# MCU.net
KiCad netlist of a schematic drawn in Altium Designer
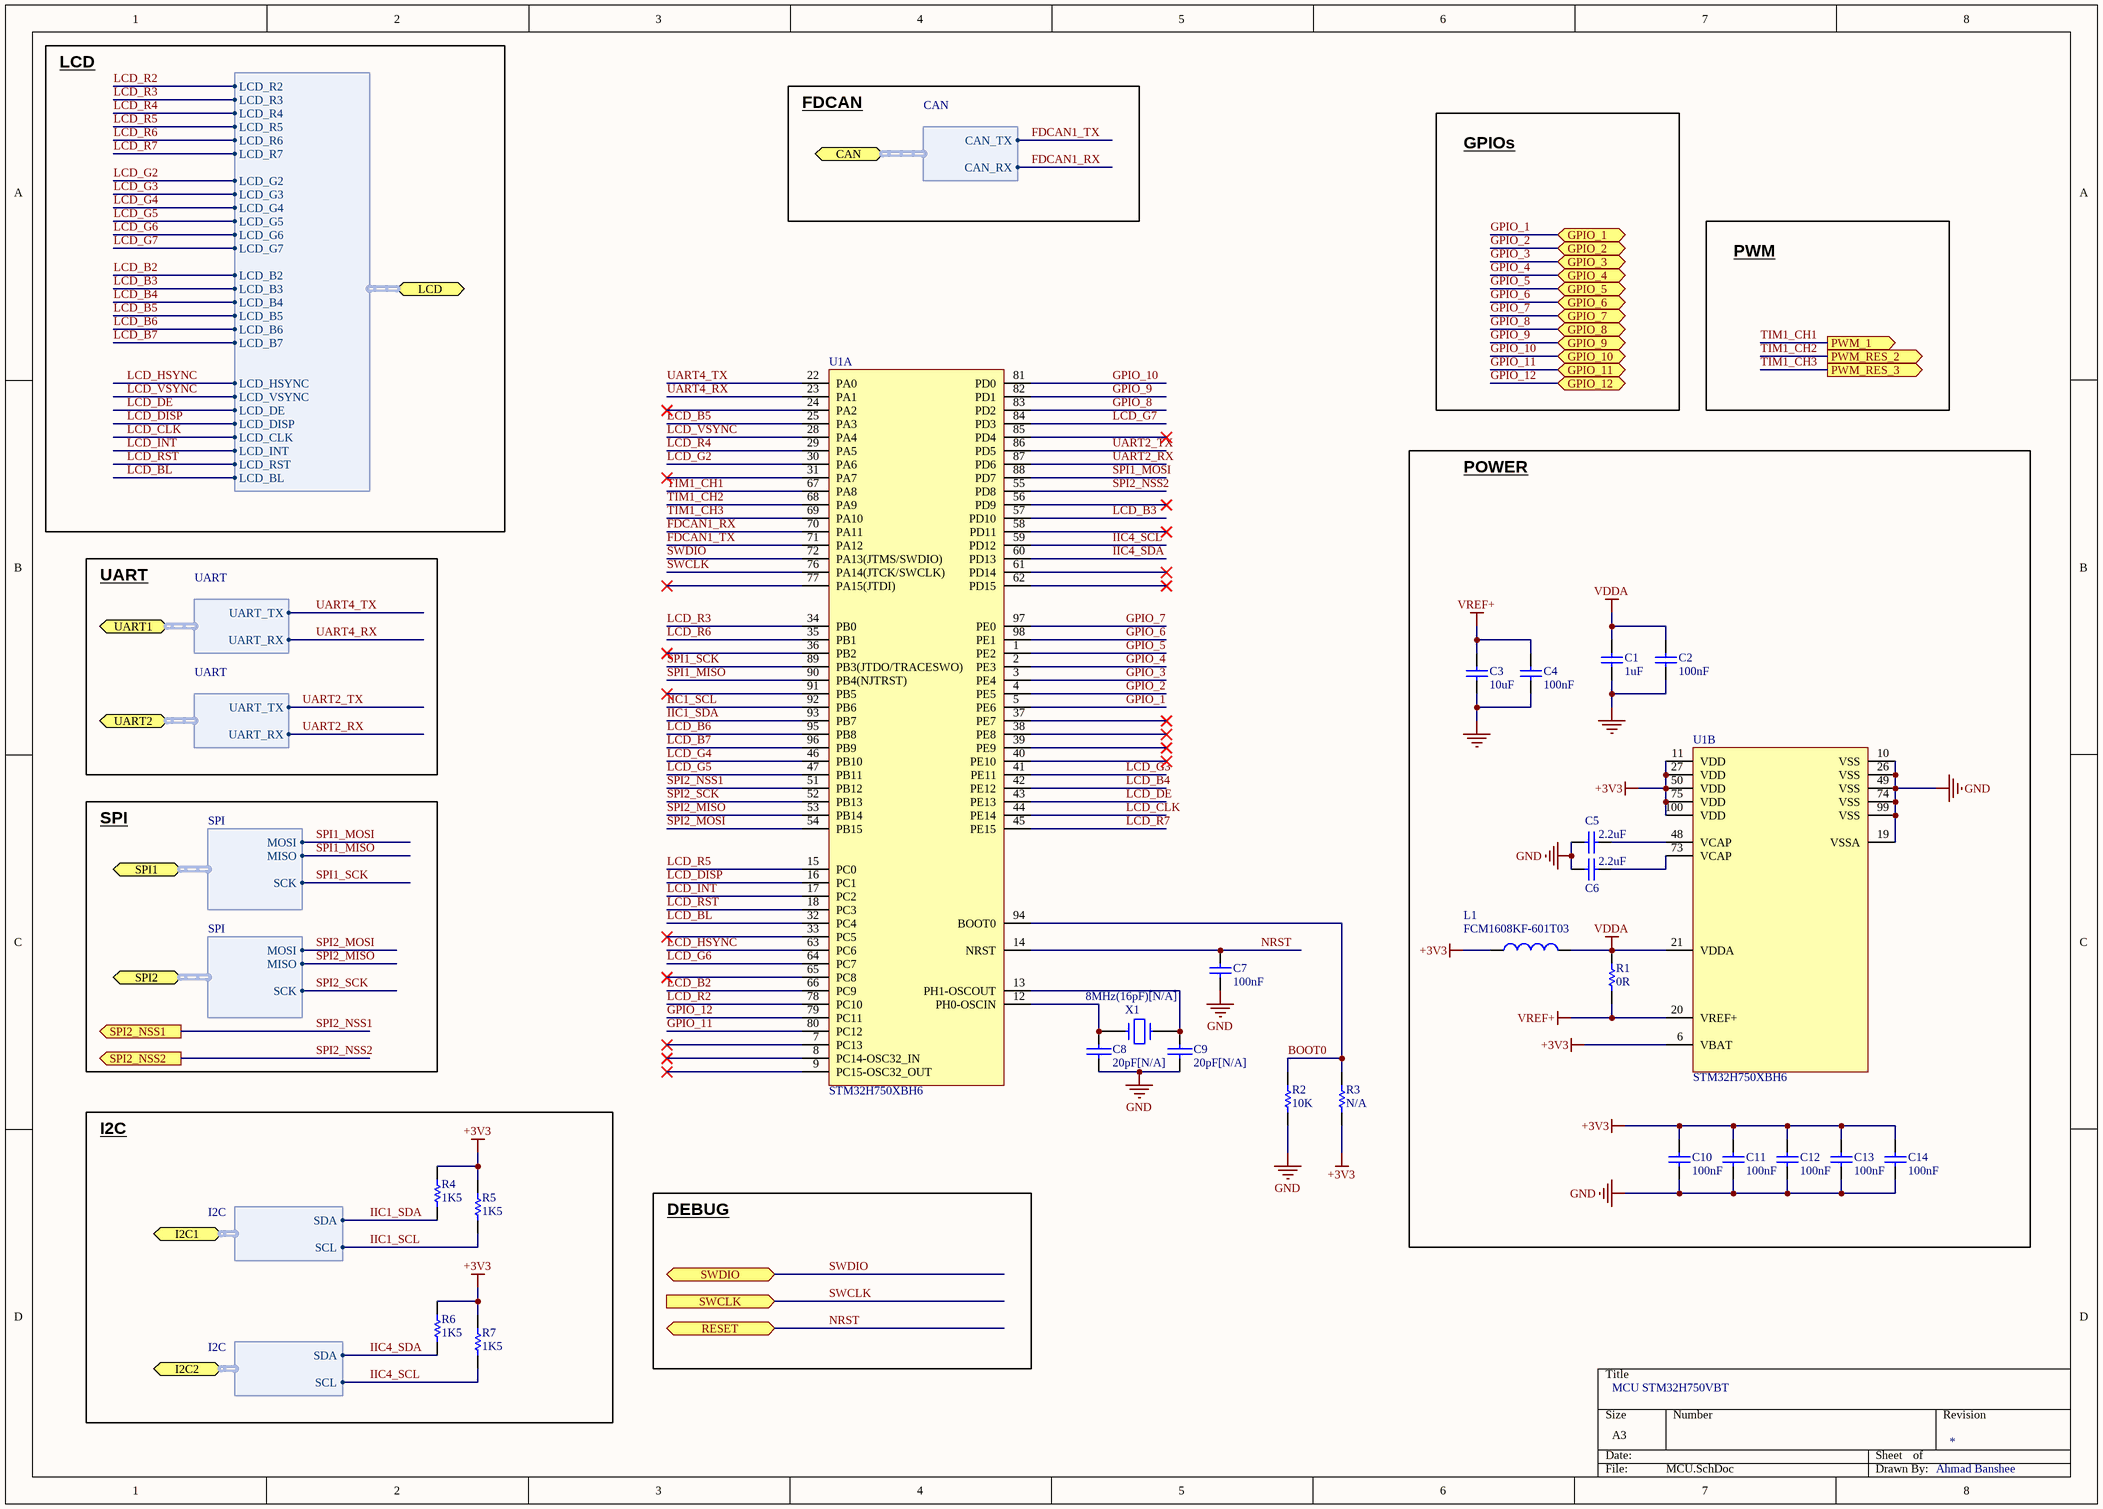
[diagram p0: MCU.SchDoc]

(export (version "E")
  (design (tool "Eeschema 10.0.6"))
  (components
    (comp (ref "C1")
      (value "1uF")
      (footprint "0805C-ST")
      (description "Capacitor, MLCC, 10uF, 25V, X5R, 10%, 0805, T=0,85mm")
      (fields
        (field (name "INTERNAL_PART_NUMBER") "MCD-00014")
        (field (name "MANUFACTURER_PART_NUMBER") "CC0805KRX5R8BB106")
        (field (name "PROVIDED_BY") "Subcon")
      )
      (libsource (lib "MCD_PARTS_database") (part "Capacitor"))
    )
    (comp (ref "C2")
      (value "100nF")
      (footprint "0603C ST")
      (description "Capacitor, MLCC, 100nF, 16V, X7R, 10%, 0402, T=0,5mm")
      (fields
        (field (name "INTERNAL_PART_NUMBER") "MCD-00102")
        (field (name "MANUFACTURER_PART_NUMBER") "CC0402KRX7R7BB104")
        (field (name "PROVIDED_BY") "Subcon")
      )
      (libsource (lib "MCD_PARTS_database") (part "Capacitor"))
    )
    (comp (ref "C3")
      (value "10uF")
      (footprint "0805C-ST")
      (description "Capacitor, MLCC, 10uF, 25V, X5R, 10%, 0805, T=0,85mm")
      (fields
        (field (name "INTERNAL_PART_NUMBER") "MCD-00014")
        (field (name "MANUFACTURER_PART_NUMBER") "CC0805KRX5R8BB106")
        (field (name "PROVIDED_BY") "Subcon")
      )
      (libsource (lib "MCD_PARTS_database") (part "Capacitor"))
    )
    (comp (ref "C4")
      (value "100nF")
      (footprint "0603C ST")
      (description "Capacitor, MLCC, 100nF, 16V, X7R, 10%, 0402, T=0,5mm")
      (fields
        (field (name "INTERNAL_PART_NUMBER") "MCD-00102")
        (field (name "MANUFACTURER_PART_NUMBER") "CC0402KRX7R7BB104")
        (field (name "PROVIDED_BY") "Subcon")
      )
      (libsource (lib "MCD_PARTS_database") (part "Capacitor"))
    )
    (comp (ref "C5")
      (value "2.2uF")
      (footprint "0603C-ST")
      (description "Capacitor, MLCC, 2.2uF, 10V, X5R, 10%, 0603, T=0,8mm")
      (fields
        (field (name "INTERNAL_PART_NUMBER") "MCD-00012")
        (field (name "MANUFACTURER_PART_NUMBER") "CC0603KRX5R6BB225")
        (field (name "PROVIDED_BY") "Subcon")
      )
      (libsource (lib "MCD_PARTS_database") (part "Capacitor"))
    )
    (comp (ref "C6")
      (value "2.2uF")
      (footprint "0603C-ST")
      (description "Capacitor, MLCC, 2.2uF, 10V, X5R, 10%, 0603, T=0,8mm")
      (fields
        (field (name "INTERNAL_PART_NUMBER") "MCD-00012")
        (field (name "MANUFACTURER_PART_NUMBER") "CC0603KRX5R6BB225")
        (field (name "PROVIDED_BY") "Subcon")
      )
      (libsource (lib "MCD_PARTS_database") (part "Capacitor"))
    )
    (comp (ref "C7")
      (value "100nF")
      (footprint "0603C ST")
      (description "Capacitor")
      (fields (field (name "PUBLISHER") "Altium Limited"))
      (libsource (lib "Miscellaneous Devices") (part "Cap"))
    )
    (comp (ref "C8")
      (value "20pF[N/A]")
      (footprint "0603C ST")
      (description "Capacitor")
      (libsource (lib "*") (part "CAP"))
    )
    (comp (ref "C9")
      (value "20pF[N/A]")
      (footprint "0603C ST")
      (description "Capacitor")
      (libsource (lib "*") (part "CAP"))
    )
    (comp (ref "C10")
      (value "100nF")
      (footprint "0603C ST")
      (description "Capacitor, MLCC, 100nF, 16V, X7R, 10%, 0402, T=0,5mm")
      (fields
        (field (name "INTERNAL_PART_NUMBER") "MCD-00102")
        (field (name "MANUFACTURER_PART_NUMBER") "CC0402KRX7R7BB104")
        (field (name "PROVIDED_BY") "Subcon")
      )
      (libsource (lib "MCD_PARTS_database") (part "Capacitor"))
    )
    (comp (ref "C11")
      (value "100nF")
      (footprint "0603C ST")
      (description "Capacitor, MLCC, 100nF, 16V, X7R, 10%, 0402, T=0,5mm")
      (fields
        (field (name "INTERNAL_PART_NUMBER") "MCD-00102")
        (field (name "MANUFACTURER_PART_NUMBER") "CC0402KRX7R7BB104")
        (field (name "PROVIDED_BY") "Subcon")
      )
      (libsource (lib "MCD_PARTS_database") (part "Capacitor"))
    )
    (comp (ref "C12")
      (value "100nF")
      (footprint "0603C ST")
      (description "Capacitor, MLCC, 100nF, 16V, X7R, 10%, 0402, T=0,5mm")
      (fields
        (field (name "INTERNAL_PART_NUMBER") "MCD-00102")
        (field (name "MANUFACTURER_PART_NUMBER") "CC0402KRX7R7BB104")
        (field (name "PROVIDED_BY") "Subcon")
      )
      (libsource (lib "MCD_PARTS_database") (part "Capacitor"))
    )
    (comp (ref "C13")
      (value "100nF")
      (footprint "0603C ST")
      (description "Capacitor, MLCC, 100nF, 16V, X7R, 10%, 0402, T=0,5mm")
      (fields
        (field (name "INTERNAL_PART_NUMBER") "MCD-00102")
        (field (name "MANUFACTURER_PART_NUMBER") "CC0402KRX7R7BB104")
        (field (name "PROVIDED_BY") "Subcon")
      )
      (libsource (lib "MCD_PARTS_database") (part "Capacitor"))
    )
    (comp (ref "C14")
      (value "100nF")
      (footprint "0603C ST")
      (description "Capacitor, MLCC, 100nF, 16V, X7R, 10%, 0402, T=0,5mm")
      (fields
        (field (name "INTERNAL_PART_NUMBER") "MCD-00102")
        (field (name "MANUFACTURER_PART_NUMBER") "CC0402KRX7R7BB104")
        (field (name "PROVIDED_BY") "Subcon")
      )
      (libsource (lib "MCD_PARTS_database") (part "Capacitor"))
    )
    (comp (ref "L1")
      (value "BEAD")
      (footprint "0603L-ST")
      (description "SMD Chip ferrite bead, 600R@100MHz +/-25%, 350mA, 500mohm DC, 0603, T=0.8mm")
      (fields
        (field (name "INTERNAL_PART_NUMBER") "MCD-00047")
        (field (name "MANUFACTURER_PART_NUMBER") "FCM1608KF-601T03")
        (field (name "MANUFACTURER") "TAI-TECH")
        (field (name "PROVIDED_BY") "Subcon")
      )
      (libsource (lib "MCD_PARTS_database") (part "BEAD"))
    )
    (comp (ref "R1")
      (value "0R")
      (footprint "0603R")
      (description "Resistor,0R,0603,ULO")
      (fields
        (field (name "INTERNAL_PART_NUMBER") "MCD-00181")
        (field (name "MANUFACTURER_PART_NUMBER") "PMR03EZPJ000")
        (field (name "PROVIDED_BY") "Subcon")
      )
      (libsource (lib "MCD_PARTS_database") (part "Resistor"))
    )
    (comp (ref "R2")
      (value "10K")
      (footprint "0603R")
      (description "Resistor,10K,0402,1%,1/16W")
      (fields
        (field (name "INTERNAL_PART_NUMBER") "MCD-00053")
        (field (name "MANUFACTURER_PART_NUMBER") "RC0402FR-0710KL")
        (field (name "PROVIDED_BY") "subcon")
      )
      (libsource (lib "MCD_PARTS_database") (part "Resistor"))
    )
    (comp (ref "R3")
      (value "N/A")
      (footprint "0603R")
      (description "Resistor,10K,0402,1%,1/16W")
      (fields
        (field (name "INTERNAL_PART_NUMBER") "MCD-00053")
        (field (name "MANUFACTURER_PART_NUMBER") "RC0402FR-0710KL")
        (field (name "PROVIDED_BY") "subcon")
      )
      (libsource (lib "MCD_PARTS_database") (part "Resistor"))
    )
    (comp (ref "R4")
      (value "1K5")
      (footprint "0603R")
      (description "Resistor,1K5,0402,1%,1/16W")
      (fields
        (field (name "INTERNAL_PART_NUMBER") "MCD-00068")
        (field (name "MANUFACTURER_PART_NUMBER") "RC0402FR-071K5L")
        (field (name "PROVIDED_BY") "Subcon")
      )
      (libsource (lib "MCD_PARTS_database") (part "Resistor"))
    )
    (comp (ref "R5")
      (value "1K5")
      (footprint "0603R")
      (description "Resistor,1K5,0402,1%,1/16W")
      (fields
        (field (name "INTERNAL_PART_NUMBER") "MCD-00068")
        (field (name "MANUFACTURER_PART_NUMBER") "RC0402FR-071K5L")
        (field (name "PROVIDED_BY") "Subcon")
      )
      (libsource (lib "MCD_PARTS_database") (part "Resistor"))
    )
    (comp (ref "R6")
      (value "1K5")
      (footprint "0603R")
      (description "Resistor,1K5,0402,1%,1/16W")
      (fields
        (field (name "INTERNAL_PART_NUMBER") "MCD-00068")
        (field (name "MANUFACTURER_PART_NUMBER") "RC0402FR-071K5L")
        (field (name "PROVIDED_BY") "Subcon")
      )
      (libsource (lib "MCD_PARTS_database") (part "Resistor"))
    )
    (comp (ref "R7")
      (value "1K5")
      (footprint "0603R")
      (description "Resistor,1K5,0402,1%,1/16W")
      (fields
        (field (name "INTERNAL_PART_NUMBER") "MCD-00068")
        (field (name "MANUFACTURER_PART_NUMBER") "RC0402FR-071K5L")
        (field (name "PROVIDED_BY") "Subcon")
      )
      (libsource (lib "MCD_PARTS_database") (part "Resistor"))
    )
    (comp (ref "U1")
      (value "STM32H750XBH6")
      (footprint "LQFP100_M")
      (description "32bit MCU TFBGA240+25")
      (fields
        (field (name "INTERNAL_PART_NUMBER") "MCD-01085")
        (field (name "MANUFACTURER_PART_NUMBER") "STM32H745XIH6")
        (field (name "PROVIDED_BY") "STM")
      )
      (libsource (lib "MB1381") (part "STM32H750VBT"))
    )
    (comp (ref "X1")
      (value "8MHz(16pF)[N/A]")
      (footprint "XTAL1")
      (description "Crystal")
      (libsource (lib "*") (part "CRYSTAL"))
    )
  )
  (nets
    (net (code "6") (name "+3V3") (class "Default")
      (node (ref "C10") (pin "2") (pinfunction "2_2") (pintype "passive"))
      (node (ref "C11") (pin "2") (pinfunction "2_2") (pintype "passive"))
      (node (ref "C12") (pin "2") (pinfunction "2_2") (pintype "passive"))
      (node (ref "C13") (pin "2") (pinfunction "2_2") (pintype "passive"))
      (node (ref "C14") (pin "2") (pinfunction "2_2") (pintype "passive"))
      (node (ref "L1") (pin "1") (pinfunction "1_1") (pintype "passive"))
      (node (ref "R3") (pin "1") (pinfunction "1_1") (pintype "passive"))
      (node (ref "R4") (pin "2") (pinfunction "2_2") (pintype "passive"))
      (node (ref "R5") (pin "2") (pinfunction "2_2") (pintype "passive"))
      (node (ref "R6") (pin "2") (pinfunction "2_2") (pintype "passive"))
      (node (ref "R7") (pin "2") (pinfunction "2_2") (pintype "passive"))
      (node (ref "U1") (pin "100") (pinfunction "VDD_100") (pintype "passive"))
      (node (ref "U1") (pin "11") (pinfunction "VDD_11") (pintype "passive"))
      (node (ref "U1") (pin "27") (pinfunction "VDD_27") (pintype "passive"))
      (node (ref "U1") (pin "50") (pinfunction "VDD_50") (pintype "passive"))
      (node (ref "U1") (pin "6") (pinfunction "VBAT_6") (pintype "passive"))
      (node (ref "U1") (pin "75") (pinfunction "VDD_75") (pintype "passive"))
    )
    (net (code "7") (name "/BOOT0") (class "Default")
      (node (ref "R2") (pin "1") (pinfunction "1_1") (pintype "passive"))
      (node (ref "R3") (pin "2") (pinfunction "2_2") (pintype "passive"))
      (node (ref "U1") (pin "94") (pinfunction "BOOT0_94") (pintype "passive"))
    )
    (net (code "8") (name "/FDCAN1_RX") (class "Default")
      (node (ref "U1") (pin "70") (pinfunction "PA11_70") (pintype "passive"))
    )
    (net (code "9") (name "/FDCAN1_TX") (class "Default")
      (node (ref "U1") (pin "71") (pinfunction "PA12_71") (pintype "passive"))
    )
    (net (code "10") (name "/GPIO_1") (class "Default")
      (node (ref "U1") (pin "5") (pinfunction "PE6_5") (pintype "passive"))
    )
    (net (code "11") (name "/GPIO_2") (class "Default")
      (node (ref "U1") (pin "4") (pinfunction "PE5_4") (pintype "passive"))
    )
    (net (code "12") (name "/GPIO_3") (class "Default")
      (node (ref "U1") (pin "3") (pinfunction "PE4_3") (pintype "passive"))
    )
    (net (code "13") (name "/GPIO_4") (class "Default")
      (node (ref "U1") (pin "2") (pinfunction "PE3_2") (pintype "passive"))
    )
    (net (code "14") (name "/GPIO_5") (class "Default")
      (node (ref "U1") (pin "1") (pinfunction "PE2_1") (pintype "passive"))
    )
    (net (code "15") (name "/GPIO_6") (class "Default")
      (node (ref "U1") (pin "98") (pinfunction "PE1_98") (pintype "passive"))
    )
    (net (code "16") (name "/GPIO_7") (class "Default")
      (node (ref "U1") (pin "97") (pinfunction "PE0_97") (pintype "passive"))
    )
    (net (code "17") (name "/GPIO_8") (class "Default")
      (node (ref "U1") (pin "83") (pinfunction "PD2_83") (pintype "passive"))
    )
    (net (code "18") (name "/GPIO_9") (class "Default")
      (node (ref "U1") (pin "82") (pinfunction "PD1_82") (pintype "passive"))
    )
    (net (code "19") (name "/GPIO_10") (class "Default")
      (node (ref "U1") (pin "81") (pinfunction "PD0_81") (pintype "passive"))
    )
    (net (code "20") (name "/GPIO_11") (class "Default")
      (node (ref "U1") (pin "80") (pinfunction "PC12_80") (pintype "passive"))
    )
    (net (code "21") (name "/GPIO_12") (class "Default")
      (node (ref "U1") (pin "79") (pinfunction "PC11_79") (pintype "passive"))
    )
    (net (code "22") (name "/IIC1_SCL") (class "Default")
      (node (ref "R5") (pin "1") (pinfunction "1_1") (pintype "passive"))
      (node (ref "U1") (pin "92") (pinfunction "PB6_92") (pintype "passive"))
    )
    (net (code "23") (name "/IIC1_SDA") (class "Default")
      (node (ref "R4") (pin "1") (pinfunction "1_1") (pintype "passive"))
      (node (ref "U1") (pin "93") (pinfunction "PB7_93") (pintype "passive"))
    )
    (net (code "24") (name "/IIC4_SCL") (class "Default")
      (node (ref "R7") (pin "1") (pinfunction "1_1") (pintype "passive"))
      (node (ref "U1") (pin "59") (pinfunction "PD12_59") (pintype "passive"))
    )
    (net (code "25") (name "/IIC4_SDA") (class "Default")
      (node (ref "R6") (pin "1") (pinfunction "1_1") (pintype "passive"))
      (node (ref "U1") (pin "60") (pinfunction "PD13_60") (pintype "passive"))
    )
    (net (code "26") (name "/LCD_B2") (class "Default")
      (node (ref "U1") (pin "66") (pinfunction "PC9_66") (pintype "passive"))
    )
    (net (code "27") (name "/LCD_B3") (class "Default")
      (node (ref "U1") (pin "57") (pinfunction "PD10_57") (pintype "passive"))
    )
    (net (code "28") (name "/LCD_B4") (class "Default")
      (node (ref "U1") (pin "42") (pinfunction "PE12_42") (pintype "passive"))
    )
    (net (code "29") (name "/LCD_B5") (class "Default")
      (node (ref "U1") (pin "25") (pinfunction "PA3_25") (pintype "passive"))
    )
    (net (code "30") (name "/LCD_B6") (class "Default")
      (node (ref "U1") (pin "95") (pinfunction "PB8_95") (pintype "passive"))
    )
    (net (code "31") (name "/LCD_B7") (class "Default")
      (node (ref "U1") (pin "96") (pinfunction "PB9_96") (pintype "passive"))
    )
    (net (code "32") (name "/LCD_BL") (class "Default")
      (node (ref "U1") (pin "32") (pinfunction "PC4_32") (pintype "passive"))
    )
    (net (code "33") (name "/LCD_CLK") (class "Default")
      (node (ref "U1") (pin "44") (pinfunction "PE14_44") (pintype "passive"))
    )
    (net (code "34") (name "/LCD_DE") (class "Default")
      (node (ref "U1") (pin "43") (pinfunction "PE13_43") (pintype "passive"))
    )
    (net (code "35") (name "/LCD_DISP") (class "Default")
      (node (ref "U1") (pin "16") (pinfunction "PC1_16") (pintype "passive"))
    )
    (net (code "36") (name "/LCD_G2") (class "Default")
      (node (ref "U1") (pin "30") (pinfunction "PA6_30") (pintype "passive"))
    )
    (net (code "37") (name "/LCD_G3") (class "Default")
      (node (ref "U1") (pin "41") (pinfunction "PE11_41") (pintype "passive"))
    )
    (net (code "38") (name "/LCD_G4") (class "Default")
      (node (ref "U1") (pin "46") (pinfunction "PB10_46") (pintype "passive"))
    )
    (net (code "39") (name "/LCD_G5") (class "Default")
      (node (ref "U1") (pin "47") (pinfunction "PB11_47") (pintype "passive"))
    )
    (net (code "40") (name "/LCD_G6") (class "Default")
      (node (ref "U1") (pin "64") (pinfunction "PC7_64") (pintype "passive"))
    )
    (net (code "41") (name "/LCD_G7") (class "Default")
      (node (ref "U1") (pin "84") (pinfunction "PD3_84") (pintype "passive"))
    )
    (net (code "42") (name "/LCD_HSYNC") (class "Default")
      (node (ref "U1") (pin "63") (pinfunction "PC6_63") (pintype "passive"))
    )
    (net (code "43") (name "/LCD_INT") (class "Default")
      (node (ref "U1") (pin "17") (pinfunction "PC2_17") (pintype "passive"))
    )
    (net (code "44") (name "/LCD_R2") (class "Default")
      (node (ref "U1") (pin "78") (pinfunction "PC10_78") (pintype "passive"))
    )
    (net (code "45") (name "/LCD_R3") (class "Default")
      (node (ref "U1") (pin "34") (pinfunction "PB0_34") (pintype "passive"))
    )
    (net (code "46") (name "/LCD_R4") (class "Default")
      (node (ref "U1") (pin "29") (pinfunction "PA5_29") (pintype "passive"))
    )
    (net (code "47") (name "/LCD_R5") (class "Default")
      (node (ref "U1") (pin "15") (pinfunction "PC0_15") (pintype "passive"))
    )
    (net (code "48") (name "/LCD_R6") (class "Default")
      (node (ref "U1") (pin "35") (pinfunction "PB1_35") (pintype "passive"))
    )
    (net (code "49") (name "/LCD_R7") (class "Default")
      (node (ref "U1") (pin "45") (pinfunction "PE15_45") (pintype "passive"))
    )
    (net (code "50") (name "/LCD_RST") (class "Default")
      (node (ref "U1") (pin "18") (pinfunction "PC3_18") (pintype "passive"))
    )
    (net (code "51") (name "/LCD_VSYNC") (class "Default")
      (node (ref "U1") (pin "28") (pinfunction "PA4_28") (pintype "passive"))
    )
    (net (code "52") (name "/NRST") (class "Default")
      (node (ref "C7") (pin "1") (pinfunction "1_1") (pintype "passive"))
      (node (ref "U1") (pin "14") (pinfunction "NRST_14") (pintype "passive"))
    )
    (net (code "53") (name "/SPI1_MISO") (class "Default")
      (node (ref "U1") (pin "90") (pinfunction "PB4(NJTRST)_90") (pintype "passive"))
    )
    (net (code "54") (name "/SPI1_MOSI") (class "Default")
      (node (ref "U1") (pin "88") (pinfunction "PD7_88") (pintype "passive"))
    )
    (net (code "55") (name "/SPI1_SCK") (class "Default")
      (node (ref "U1") (pin "89") (pinfunction "PB3(JTDO/TRACESWO)_89") (pintype "passive"))
    )
    (net (code "56") (name "/SPI2_MISO") (class "Default")
      (node (ref "U1") (pin "53") (pinfunction "PB14_53") (pintype "passive"))
    )
    (net (code "57") (name "/SPI2_MOSI") (class "Default")
      (node (ref "U1") (pin "54") (pinfunction "PB15_54") (pintype "passive"))
    )
    (net (code "58") (name "/SPI2_NSS1") (class "Default")
      (node (ref "U1") (pin "51") (pinfunction "PB12_51") (pintype "passive"))
    )
    (net (code "59") (name "/SPI2_NSS2") (class "Default")
      (node (ref "U1") (pin "55") (pinfunction "PD8_55") (pintype "passive"))
    )
    (net (code "60") (name "/SPI2_SCK") (class "Default")
      (node (ref "U1") (pin "52") (pinfunction "PB13_52") (pintype "passive"))
    )
    (net (code "61") (name "/SWCLK") (class "Default")
      (node (ref "U1") (pin "76") (pinfunction "PA14(JTCK/SWCLK)_76") (pintype "passive"))
    )
    (net (code "62") (name "/SWDIO") (class "Default")
      (node (ref "U1") (pin "72") (pinfunction "PA13(JTMS/SWDIO)_72") (pintype "passive"))
    )
    (net (code "63") (name "/TIM1_CH1") (class "Default")
      (node (ref "U1") (pin "67") (pinfunction "PA8_67") (pintype "passive"))
    )
    (net (code "64") (name "/TIM1_CH2") (class "Default")
      (node (ref "U1") (pin "68") (pinfunction "PA9_68") (pintype "passive"))
    )
    (net (code "65") (name "/TIM1_CH3") (class "Default")
      (node (ref "U1") (pin "69") (pinfunction "PA10_69") (pintype "passive"))
    )
    (net (code "66") (name "/UART2_RX") (class "Default")
      (node (ref "U1") (pin "87") (pinfunction "PD6_87") (pintype "passive"))
    )
    (net (code "67") (name "/UART2_TX") (class "Default")
      (node (ref "U1") (pin "86") (pinfunction "PD5_86") (pintype "passive"))
    )
    (net (code "68") (name "/UART4_RX") (class "Default")
      (node (ref "U1") (pin "23") (pinfunction "PA1_23") (pintype "passive"))
    )
    (net (code "69") (name "/UART4_TX") (class "Default")
      (node (ref "U1") (pin "22") (pinfunction "PA0_22") (pintype "passive"))
    )
    (net (code "75") (name "GND") (class "Default")
      (node (ref "C1") (pin "1") (pinfunction "1_1") (pintype "passive"))
      (node (ref "C10") (pin "1") (pinfunction "1_1") (pintype "passive"))
      (node (ref "C11") (pin "1") (pinfunction "1_1") (pintype "passive"))
      (node (ref "C12") (pin "1") (pinfunction "1_1") (pintype "passive"))
      (node (ref "C13") (pin "1") (pinfunction "1_1") (pintype "passive"))
      (node (ref "C14") (pin "1") (pinfunction "1_1") (pintype "passive"))
      (node (ref "C2") (pin "1") (pinfunction "1_1") (pintype "passive"))
      (node (ref "C3") (pin "1") (pinfunction "1_1") (pintype "passive"))
      (node (ref "C4") (pin "1") (pinfunction "1_1") (pintype "passive"))
      (node (ref "C5") (pin "1") (pinfunction "1_1") (pintype "passive"))
      (node (ref "C6") (pin "1") (pinfunction "1_1") (pintype "passive"))
      (node (ref "C7") (pin "2") (pinfunction "2_2") (pintype "passive"))
      (node (ref "C8") (pin "1") (pinfunction "1_1") (pintype "passive"))
      (node (ref "C9") (pin "1") (pinfunction "1_1") (pintype "passive"))
      (node (ref "R2") (pin "2") (pinfunction "2_2") (pintype "passive"))
      (node (ref "U1") (pin "10") (pinfunction "VSS_10") (pintype "passive"))
      (node (ref "U1") (pin "19") (pinfunction "VSSA_19") (pintype "passive"))
      (node (ref "U1") (pin "26") (pinfunction "VSS_26") (pintype "passive"))
      (node (ref "U1") (pin "49") (pinfunction "VSS_49") (pintype "passive"))
      (node (ref "U1") (pin "74") (pinfunction "VSS_74") (pintype "passive"))
      (node (ref "U1") (pin "99") (pinfunction "VSS_99") (pintype "passive"))
    )
    (net (code "76") (name "Net-(C5-Pad2)") (class "Default")
      (node (ref "C5") (pin "2") (pinfunction "2_2") (pintype "passive"))
      (node (ref "U1") (pin "48") (pinfunction "VCAP_48") (pintype "passive"))
    )
    (net (code "77") (name "Net-(C6-Pad2)") (class "Default")
      (node (ref "C6") (pin "2") (pinfunction "2_2") (pintype "passive"))
      (node (ref "U1") (pin "73") (pinfunction "VCAP_73") (pintype "passive"))
    )
    (net (code "78") (name "Net-(U1A-PH0-OSCIN)") (class "Default")
      (node (ref "C8") (pin "2") (pinfunction "2_2") (pintype "passive"))
      (node (ref "U1") (pin "12") (pinfunction "PH0-OSCIN_12") (pintype "passive"))
      (node (ref "X1") (pin "1") (pinfunction "1_1") (pintype "passive"))
    )
    (net (code "79") (name "Net-(U1A-PH1-OSCOUT)") (class "Default")
      (node (ref "C9") (pin "2") (pinfunction "2_2") (pintype "passive"))
      (node (ref "U1") (pin "13") (pinfunction "PH1-OSCOUT_13") (pintype "passive"))
      (node (ref "X1") (pin "2") (pinfunction "2_2") (pintype "passive"))
    )
    (net (code "80") (name "VDDA") (class "Default")
      (node (ref "C1") (pin "2") (pinfunction "2_2") (pintype "passive"))
      (node (ref "C2") (pin "2") (pinfunction "2_2") (pintype "passive"))
      (node (ref "L1") (pin "2") (pinfunction "2_2") (pintype "passive"))
      (node (ref "R1") (pin "1") (pinfunction "1_1") (pintype "passive"))
      (node (ref "U1") (pin "21") (pinfunction "VDDA_21") (pintype "passive"))
    )
    (net (code "81") (name "VREF+") (class "Default")
      (node (ref "C3") (pin "2") (pinfunction "2_2") (pintype "passive"))
      (node (ref "C4") (pin "2") (pinfunction "2_2") (pintype "passive"))
      (node (ref "R1") (pin "2") (pinfunction "2_2") (pintype "passive"))
      (node (ref "U1") (pin "20") (pinfunction "VREF+_20") (pintype "passive"))
    )
    (net (code "82") (name "unconnected-(U1A-PA2-Pad24)") (class "Default")
      (node (ref "U1") (pin "24") (pinfunction "PA2_24") (pintype "passive+no_connect"))
    )
    (net (code "83") (name "unconnected-(U1A-PA7-Pad31)") (class "Default")
      (node (ref "U1") (pin "31") (pinfunction "PA7_31") (pintype "passive+no_connect"))
    )
    (net (code "84") (name "unconnected-(U1A-PA15(JTDI)-Pad77)") (class "Default")
      (node (ref "U1") (pin "77") (pinfunction "PA15(JTDI)_77") (pintype "passive+no_connect"))
    )
    (net (code "85") (name "unconnected-(U1A-PB2-Pad36)") (class "Default")
      (node (ref "U1") (pin "36") (pinfunction "PB2_36") (pintype "passive+no_connect"))
    )
    (net (code "86") (name "unconnected-(U1A-PB5-Pad91)") (class "Default")
      (node (ref "U1") (pin "91") (pinfunction "PB5_91") (pintype "passive+no_connect"))
    )
    (net (code "87") (name "unconnected-(U1A-PC5-Pad33)") (class "Default")
      (node (ref "U1") (pin "33") (pinfunction "PC5_33") (pintype "passive+no_connect"))
    )
    (net (code "88") (name "unconnected-(U1A-PC8-Pad65)") (class "Default")
      (node (ref "U1") (pin "65") (pinfunction "PC8_65") (pintype "passive+no_connect"))
    )
    (net (code "89") (name "unconnected-(U1A-PC13-Pad7)") (class "Default")
      (node (ref "U1") (pin "7") (pinfunction "PC13_7") (pintype "passive+no_connect"))
    )
    (net (code "90") (name "unconnected-(U1A-PC14-OSC32_IN-Pad8)") (class "Default")
      (node (ref "U1") (pin "8") (pinfunction "PC14-OSC32_IN_8") (pintype "passive+no_connect"))
    )
    (net (code "91") (name "unconnected-(U1A-PC15-OSC32_OUT-Pad9)") (class "Default")
      (node (ref "U1") (pin "9") (pinfunction "PC15-OSC32_OUT_9") (pintype "passive+no_connect"))
    )
    (net (code "92") (name "unconnected-(U1A-PD4-Pad85)") (class "Default")
      (node (ref "U1") (pin "85") (pinfunction "PD4_85") (pintype "passive+no_connect"))
    )
    (net (code "93") (name "unconnected-(U1A-PD9-Pad56)") (class "Default")
      (node (ref "U1") (pin "56") (pinfunction "PD9_56") (pintype "passive+no_connect"))
    )
    (net (code "94") (name "unconnected-(U1A-PD11-Pad58)") (class "Default")
      (node (ref "U1") (pin "58") (pinfunction "PD11_58") (pintype "passive+no_connect"))
    )
    (net (code "95") (name "unconnected-(U1A-PD14-Pad61)") (class "Default")
      (node (ref "U1") (pin "61") (pinfunction "PD14_61") (pintype "passive+no_connect"))
    )
    (net (code "96") (name "unconnected-(U1A-PD15-Pad62)") (class "Default")
      (node (ref "U1") (pin "62") (pinfunction "PD15_62") (pintype "passive+no_connect"))
    )
    (net (code "97") (name "unconnected-(U1A-PE7-Pad37)") (class "Default")
      (node (ref "U1") (pin "37") (pinfunction "PE7_37") (pintype "passive+no_connect"))
    )
    (net (code "98") (name "unconnected-(U1A-PE8-Pad38)") (class "Default")
      (node (ref "U1") (pin "38") (pinfunction "PE8_38") (pintype "passive+no_connect"))
    )
    (net (code "99") (name "unconnected-(U1A-PE9-Pad39)") (class "Default")
      (node (ref "U1") (pin "39") (pinfunction "PE9_39") (pintype "passive+no_connect"))
    )
    (net (code "100") (name "unconnected-(U1A-PE10-Pad40)") (class "Default")
      (node (ref "U1") (pin "40") (pinfunction "PE10_40") (pintype "passive+no_connect"))
    )
  )
)
